# Aystable.net
KiCad netlist of a schematic drawn in EAGLE
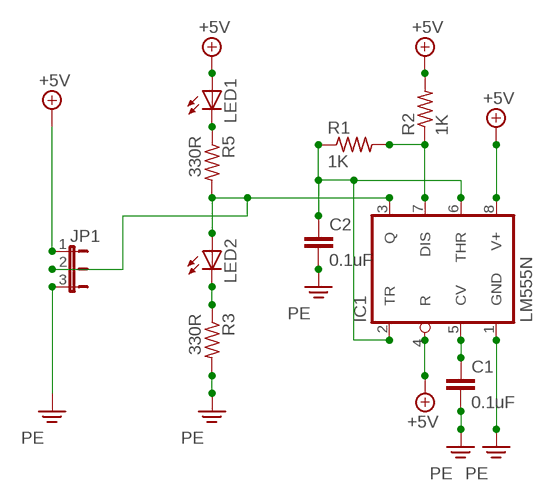
[diagram p0: schematic, sheet 1]

(export (version "E")
  (design (tool "Eeschema 10.0.6"))
  (components
    (comp (ref "C1")
      (value "0.1uF")
      (footprint "eagle-import:C075-032X103")
      (libsource (lib "eagle-import") (part "C-EU075-032X103"))
    )
    (comp (ref "C2")
      (value "0.1uF")
      (footprint "eagle-import:C075-032X103")
      (libsource (lib "eagle-import") (part "C-EU075-032X103"))
    )
    (comp (ref "IC1")
      (value "LM555N")
      (footprint "eagle-import:DIL08")
      (libsource (lib "eagle-import") (part "555NLM"))
    )
    (comp (ref "JP1")
      (value "JP2E")
      (footprint "eagle-import:JP2")
      (libsource (lib "eagle-import") (part "JP2E"))
    )
    (comp (ref "LED1")
      (value "LED5MM")
      (footprint "eagle-import:LED5MM")
      (libsource (lib "eagle-import") (part "LED5MM"))
    )
    (comp (ref "LED2")
      (value "LED5MM")
      (footprint "eagle-import:LED5MM")
      (libsource (lib "eagle-import") (part "LED5MM"))
    )
    (comp (ref "R1")
      (value "1K")
      (footprint "eagle-import:0207_10")
      (libsource (lib "eagle-import") (part "R-US_0207/10"))
    )
    (comp (ref "R2")
      (value "1K")
      (footprint "eagle-import:0207_10")
      (libsource (lib "eagle-import") (part "R-US_0207/10"))
    )
    (comp (ref "R3")
      (value "330R")
      (footprint "eagle-import:0207_10")
      (libsource (lib "eagle-import") (part "R-US_0207/10"))
    )
    (comp (ref "R5")
      (value "330R")
      (footprint "eagle-import:0207_10")
      (libsource (lib "eagle-import") (part "R-US_0207/10"))
    )
  )
  (nets
    (net (code "1") (name "+5V") (class "Default")
      (node (ref "IC1") (pin "4") (pinfunction "R_4") (pintype "input"))
      (node (ref "IC1") (pin "8") (pinfunction "V+_8") (pintype "power_in"))
      (node (ref "JP1") (pin "1") (pinfunction "1_1") (pintype "passive"))
      (node (ref "LED1") (pin "A") (pinfunction "A_A") (pintype "passive"))
      (node (ref "R2") (pin "2") (pinfunction "2_2") (pintype "passive"))
    )
    (net (code "2") (name "Net-(IC1-CV)") (class "Default")
      (node (ref "C1") (pin "1") (pinfunction "1_1") (pintype "passive"))
      (node (ref "IC1") (pin "5") (pinfunction "CV_5") (pintype "input"))
    )
    (net (code "3") (name "Net-(IC1-DIS)") (class "Default")
      (node (ref "IC1") (pin "7") (pinfunction "DIS_7") (pintype "input"))
      (node (ref "R1") (pin "2") (pinfunction "2_2") (pintype "passive"))
      (node (ref "R2") (pin "1") (pinfunction "1_1") (pintype "passive"))
    )
    (net (code "4") (name "Net-(IC1-Q)") (class "Default")
      (node (ref "IC1") (pin "3") (pinfunction "Q_3") (pintype "output"))
      (node (ref "JP1") (pin "2") (pinfunction "2_2") (pintype "passive"))
      (node (ref "LED2") (pin "A") (pinfunction "A_A") (pintype "passive"))
      (node (ref "R5") (pin "2") (pinfunction "2_2") (pintype "passive"))
    )
    (net (code "5") (name "Net-(IC1-THR)") (class "Default")
      (node (ref "C2") (pin "1") (pinfunction "1_1") (pintype "passive"))
      (node (ref "IC1") (pin "2") (pinfunction "TR_2") (pintype "input"))
      (node (ref "IC1") (pin "6") (pinfunction "THR_6") (pintype "input"))
      (node (ref "R1") (pin "1") (pinfunction "1_1") (pintype "passive"))
    )
    (net (code "6") (name "Net-(LED1-C)") (class "Default")
      (node (ref "LED1") (pin "K") (pinfunction "C_K") (pintype "passive"))
      (node (ref "R5") (pin "1") (pinfunction "1_1") (pintype "passive"))
    )
    (net (code "7") (name "Net-(LED2-C)") (class "Default")
      (node (ref "LED2") (pin "K") (pinfunction "C_K") (pintype "passive"))
      (node (ref "R3") (pin "1") (pinfunction "1_1") (pintype "passive"))
    )
    (net (code "8") (name "PE") (class "Default")
      (node (ref "C1") (pin "2") (pinfunction "2_2") (pintype "passive"))
      (node (ref "C2") (pin "2") (pinfunction "2_2") (pintype "passive"))
      (node (ref "IC1") (pin "1") (pinfunction "GND_1") (pintype "power_in"))
      (node (ref "JP1") (pin "3") (pinfunction "3_3") (pintype "passive"))
      (node (ref "R3") (pin "2") (pinfunction "2_2") (pintype "passive"))
    )
  )
)
